# Amplifecation.net
KiCad netlist of a schematic drawn in Altium Designer
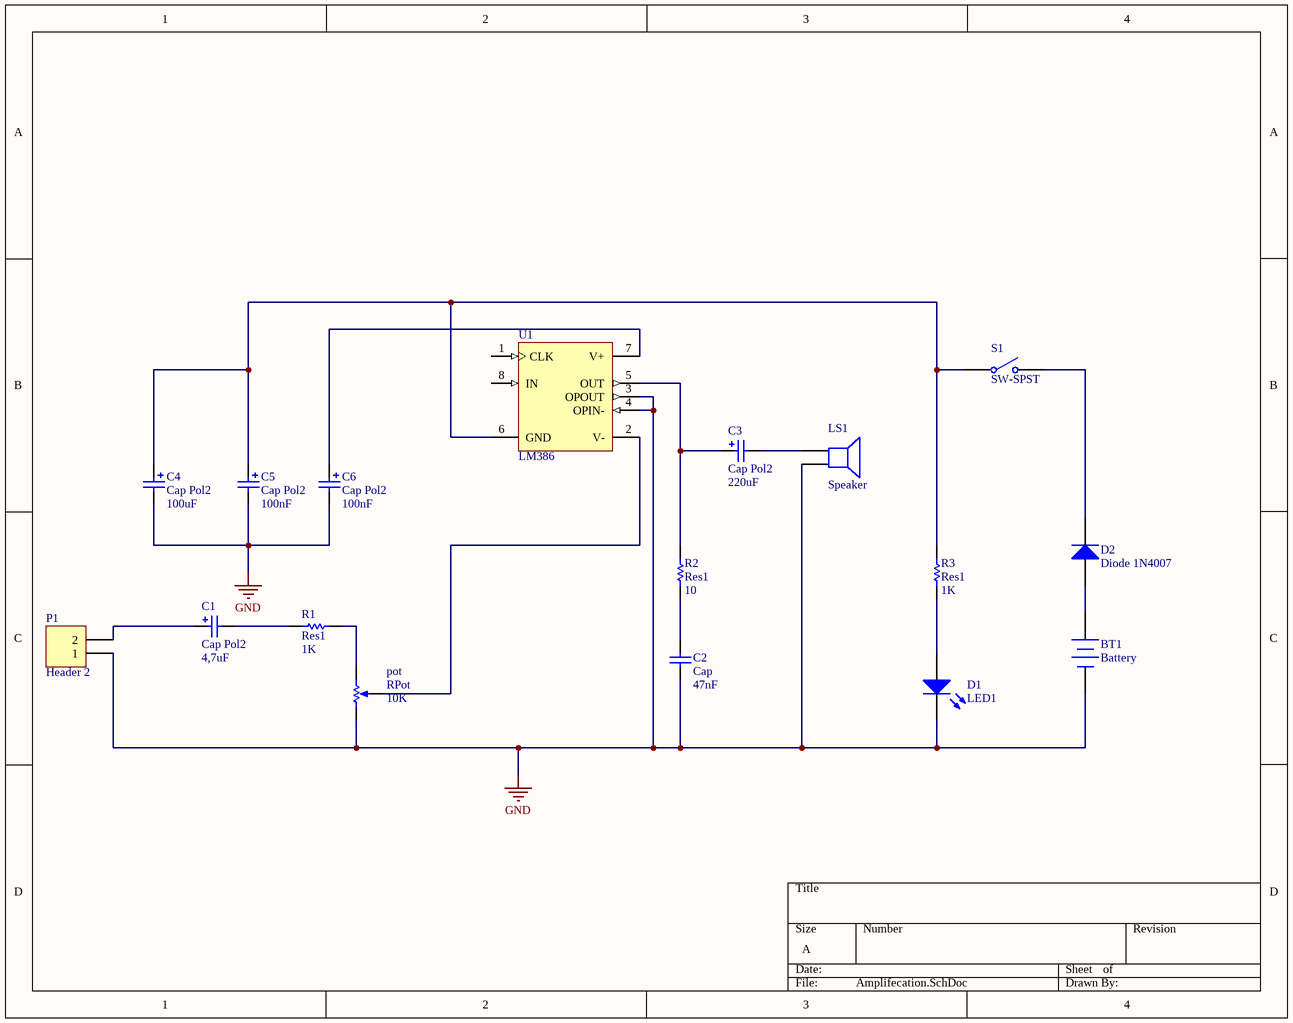
[diagram p0: Amplifecation.SchDoc]

(export (version "E")
  (design (tool "Eeschema 10.0.6"))
  (components
    (comp (ref "BT1")
      (value "Battery")
      (footprint "BAT-2")
      (description "Multicell Battery")
      (fields (field (name "PUBLISHER") "Altium Limited"))
      (libsource (lib "Miscellaneous Devices") (part "Battery"))
    )
    (comp (ref "C1")
      (value "Cap Pol2")
      (footprint "POLAR0.8")
      (description "Polarized Capacitor (Axial)")
      (fields (field (name "ALTIUM_VALUE") "4,7uF") (field (name "PUBLISHER") "Altium Limited"))
      (libsource (lib "Miscellaneous Devices") (part "Cap Pol2"))
    )
    (comp (ref "C2")
      (value "Cap")
      (footprint "RAD-0.3")
      (description "Capacitor")
      (fields (field (name "ALTIUM_VALUE") "47nF") (field (name "PUBLISHER") "Altium Limited"))
      (libsource (lib "Miscellaneous Devices") (part "Cap"))
    )
    (comp (ref "C3")
      (value "Cap Pol2")
      (footprint "POLAR0.8")
      (description "Polarized Capacitor (Axial)")
      (fields (field (name "ALTIUM_VALUE") "220uF") (field (name "PUBLISHER") "Altium Limited"))
      (libsource (lib "Miscellaneous Devices") (part "Cap Pol2"))
    )
    (comp (ref "C4")
      (value "Cap Pol2")
      (footprint "POLAR0.8")
      (description "Polarized Capacitor (Axial)")
      (fields (field (name "ALTIUM_VALUE") "100uF") (field (name "PUBLISHER") "Altium Limited"))
      (libsource (lib "Miscellaneous Devices") (part "Cap Pol2"))
    )
    (comp (ref "C5")
      (value "Cap Pol2")
      (footprint "POLAR0.8")
      (description "Polarized Capacitor (Axial)")
      (fields (field (name "ALTIUM_VALUE") "100nF") (field (name "PUBLISHER") "Altium Limited"))
      (libsource (lib "Miscellaneous Devices") (part "Cap Pol2"))
    )
    (comp (ref "C6")
      (value "Cap Pol2")
      (footprint "POLAR0.8")
      (description "Polarized Capacitor (Axial)")
      (fields (field (name "ALTIUM_VALUE") "100nF") (field (name "PUBLISHER") "Altium Limited"))
      (libsource (lib "Miscellaneous Devices") (part "Cap Pol2"))
    )
    (comp (ref "D1")
      (value "LED1")
      (footprint "LED-1")
      (description "Typical RED GaAs LED")
      (fields (field (name "PUBLISHER") "Altium Limited"))
      (libsource (lib "Miscellaneous Devices") (part "LED1"))
    )
    (comp (ref "D2")
      (value "Diode 1N4007")
      (footprint "DO-41")
      (description "1 Amp General Purpose Rectifier")
      (fields (field (name "PUBLISHER") "Altium Limited"))
      (libsource (lib "Miscellaneous Devices") (part "Diode 1N4007"))
    )
    (comp (ref "LS1")
      (value "Speaker")
      (footprint "PIN2")
      (description "Loudspeaker")
      (fields (field (name "PUBLISHER") "Altium Limited"))
      (libsource (lib "Miscellaneous Devices") (part "Speaker"))
    )
    (comp (ref "P1")
      (value "Header 2")
      (footprint "HDR1X2")
      (description "Header, 2-Pin")
      (fields (field (name "PUBLISHER") "Altium Limited"))
      (libsource (lib "Miscellaneous Connectors") (part "Header 2"))
    )
    (comp (ref "pot")
      (value "RPot")
      (footprint "VR5")
      (description "Potentiometer")
      (fields (field (name "ALTIUM_VALUE") "10K") (field (name "PUBLISHER") "Altium Limited"))
      (libsource (lib "Miscellaneous Devices") (part "RPot"))
    )
    (comp (ref "R1")
      (value "Res1")
      (footprint "AXIAL-0.3")
      (description "Resistor")
      (fields (field (name "ALTIUM_VALUE") "1K") (field (name "PUBLISHER") "Altium Limited"))
      (libsource (lib "Miscellaneous Devices") (part "Res1"))
    )
    (comp (ref "R2")
      (value "Res1")
      (footprint "AXIAL-0.3")
      (description "Resistor")
      (fields (field (name "ALTIUM_VALUE") "10") (field (name "PUBLISHER") "Altium Limited"))
      (libsource (lib "Miscellaneous Devices") (part "Res1"))
    )
    (comp (ref "R3")
      (value "Res1")
      (footprint "AXIAL-0.3")
      (description "Resistor")
      (fields (field (name "ALTIUM_VALUE") "1K") (field (name "PUBLISHER") "Altium Limited"))
      (libsource (lib "Miscellaneous Devices") (part "Res1"))
    )
    (comp (ref "S1")
      (value "SW-SPST")
      (footprint "SPST-2")
      (description "Single-Pole, Single-Throw Switch")
      (fields (field (name "PUBLISHER") "Altium Limited"))
      (libsource (lib "Miscellaneous Devices") (part "SW-SPST"))
    )
    (comp (ref "U1")
      (value "LM386")
      (footprint "PA8")
      (description "8th-Order, Lowpass, Switched-Capacitor Filter")
      (fields (field (name "PUBLISHER") "Altium Limited"))
      (libsource (lib "Maxim Filter Switched Capacitor") (part "MAX291CPA"))
    )
  )
  (nets
    (net (code "1") (name "GND") (class "Default")
      (node (ref "BT1") (pin "2") (pinfunction "-_2") (pintype "passive"))
      (node (ref "C2") (pin "1") (pinfunction "1_1") (pintype "passive"))
      (node (ref "C4") (pin "2") (pinfunction "2_2") (pintype "passive"))
      (node (ref "C5") (pin "2") (pinfunction "2_2") (pintype "passive"))
      (node (ref "C6") (pin "2") (pinfunction "2_2") (pintype "passive"))
      (node (ref "D1") (pin "2") (pinfunction "K_2") (pintype "passive"))
      (node (ref "LS1") (pin "2") (pinfunction "2_2") (pintype "passive"))
      (node (ref "P1") (pin "1") (pinfunction "1_1") (pintype "passive"))
      (node (ref "U1") (pin "3") (pinfunction "OPOUT_3") (pintype "output"))
      (node (ref "U1") (pin "4") (pinfunction "OPIN-_4") (pintype "input"))
      (node (ref "pot") (pin "1") (pinfunction "TOP_1") (pintype "passive"))
    )
    (net (code "2") (name "Net-(BT1-+)") (class "Default")
      (node (ref "BT1") (pin "1") (pinfunction "+_1") (pintype "passive"))
      (node (ref "D2") (pin "1") (pinfunction "A_1") (pintype "passive"))
    )
    (net (code "3") (name "Net-(C1-Pad1)") (class "Default")
      (node (ref "C1") (pin "1") (pinfunction "1_1") (pintype "passive"))
      (node (ref "P1") (pin "2") (pinfunction "2_2") (pintype "passive"))
    )
    (net (code "4") (name "Net-(C1-Pad2)") (class "Default")
      (node (ref "C1") (pin "2") (pinfunction "2_2") (pintype "passive"))
      (node (ref "R1") (pin "1") (pinfunction "1_1") (pintype "passive"))
    )
    (net (code "5") (name "Net-(C2-Pad2)") (class "Default")
      (node (ref "C2") (pin "2") (pinfunction "2_2") (pintype "passive"))
      (node (ref "R2") (pin "1") (pinfunction "1_1") (pintype "passive"))
    )
    (net (code "6") (name "Net-(C3-Pad2)") (class "Default")
      (node (ref "C3") (pin "2") (pinfunction "2_2") (pintype "passive"))
      (node (ref "LS1") (pin "1") (pinfunction "1_1") (pintype "passive"))
    )
    (net (code "7") (name "Net-(D1-A)") (class "Default")
      (node (ref "D1") (pin "1") (pinfunction "A_1") (pintype "passive"))
      (node (ref "R3") (pin "1") (pinfunction "1_1") (pintype "passive"))
    )
    (net (code "8") (name "Net-(D2-K)") (class "Default")
      (node (ref "D2") (pin "2") (pinfunction "K_2") (pintype "passive"))
      (node (ref "S1") (pin "2") (pinfunction "NO_2") (pintype "passive"))
    )
    (net (code "9") (name "Net-(S1-COMMON)") (class "Default")
      (node (ref "C4") (pin "1") (pinfunction "1_1") (pintype "passive"))
      (node (ref "C5") (pin "1") (pinfunction "1_1") (pintype "passive"))
      (node (ref "R3") (pin "2") (pinfunction "2_2") (pintype "passive"))
      (node (ref "S1") (pin "1") (pinfunction "COMMON_1") (pintype "passive"))
      (node (ref "U1") (pin "6") (pinfunction "GND_6") (pintype "power_in"))
    )
    (net (code "10") (name "Net-(U1-OUT)") (class "Default")
      (node (ref "C3") (pin "1") (pinfunction "1_1") (pintype "passive"))
      (node (ref "R2") (pin "2") (pinfunction "2_2") (pintype "passive"))
      (node (ref "U1") (pin "5") (pinfunction "OUT_5") (pintype "output"))
    )
    (net (code "11") (name "Net-(U1-V+)") (class "Default")
      (node (ref "C6") (pin "1") (pinfunction "1_1") (pintype "passive"))
      (node (ref "U1") (pin "7") (pinfunction "V+_7") (pintype "power_in"))
    )
    (net (code "12") (name "Net-(U1-V-)") (class "Default")
      (node (ref "U1") (pin "2") (pinfunction "V-_2") (pintype "power_in"))
      (node (ref "pot") (pin "3") (pinfunction "TAP_3") (pintype "passive"))
    )
    (net (code "13") (name "Net-(pot-BOT)") (class "Default")
      (node (ref "R1") (pin "2") (pinfunction "2_2") (pintype "passive"))
      (node (ref "pot") (pin "2") (pinfunction "BOT_2") (pintype "passive"))
    )
    (net (code "14") (name "unconnected-(U1-CLK-Pad1)") (class "Default")
      (node (ref "U1") (pin "1") (pinfunction "CLK_1") (pintype "input"))
    )
    (net (code "15") (name "unconnected-(U1-IN-Pad8)") (class "Default")
      (node (ref "U1") (pin "8") (pinfunction "IN_8") (pintype "input"))
    )
  )
)
